# -CIU_20260909.net
KiCad netlist of a schematic drawn in Altium Designer
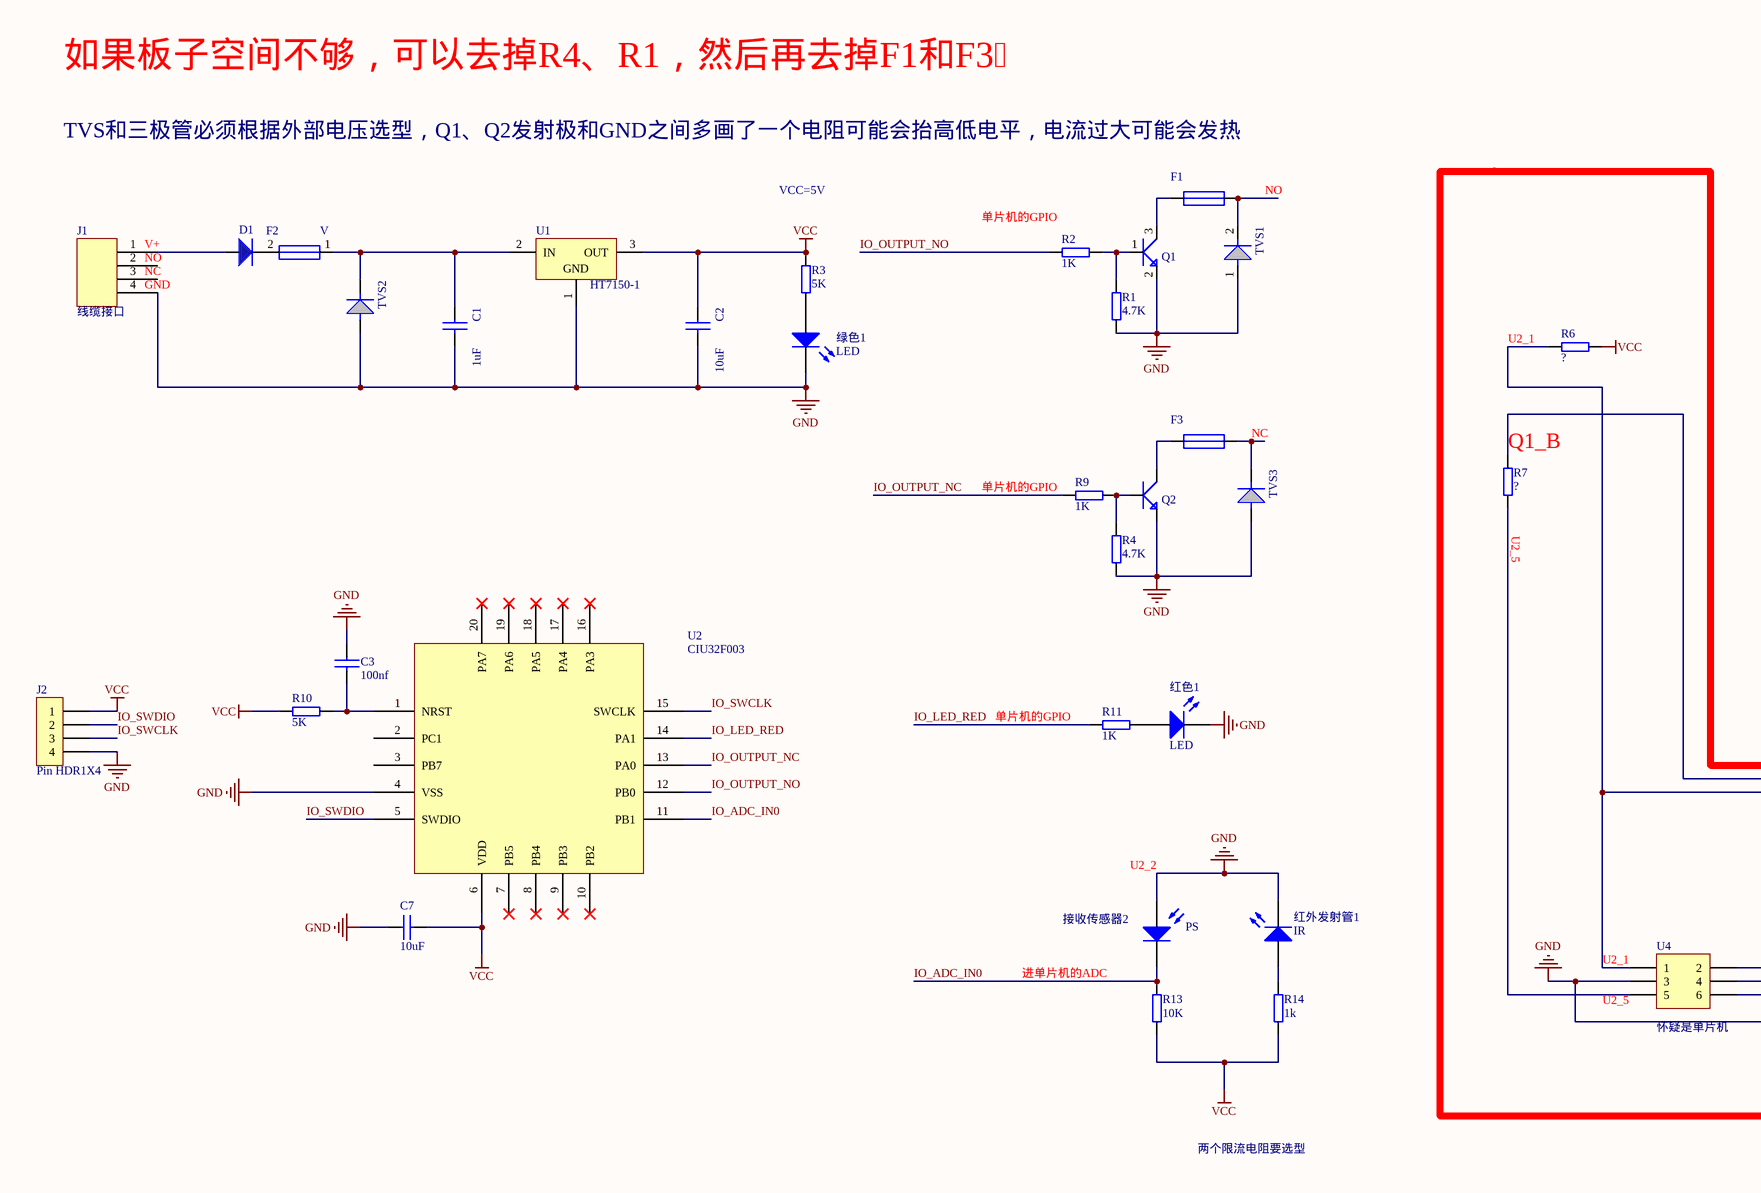
[diagram p0: 槽形开关-CIU版本20260909.SchDoc, left]
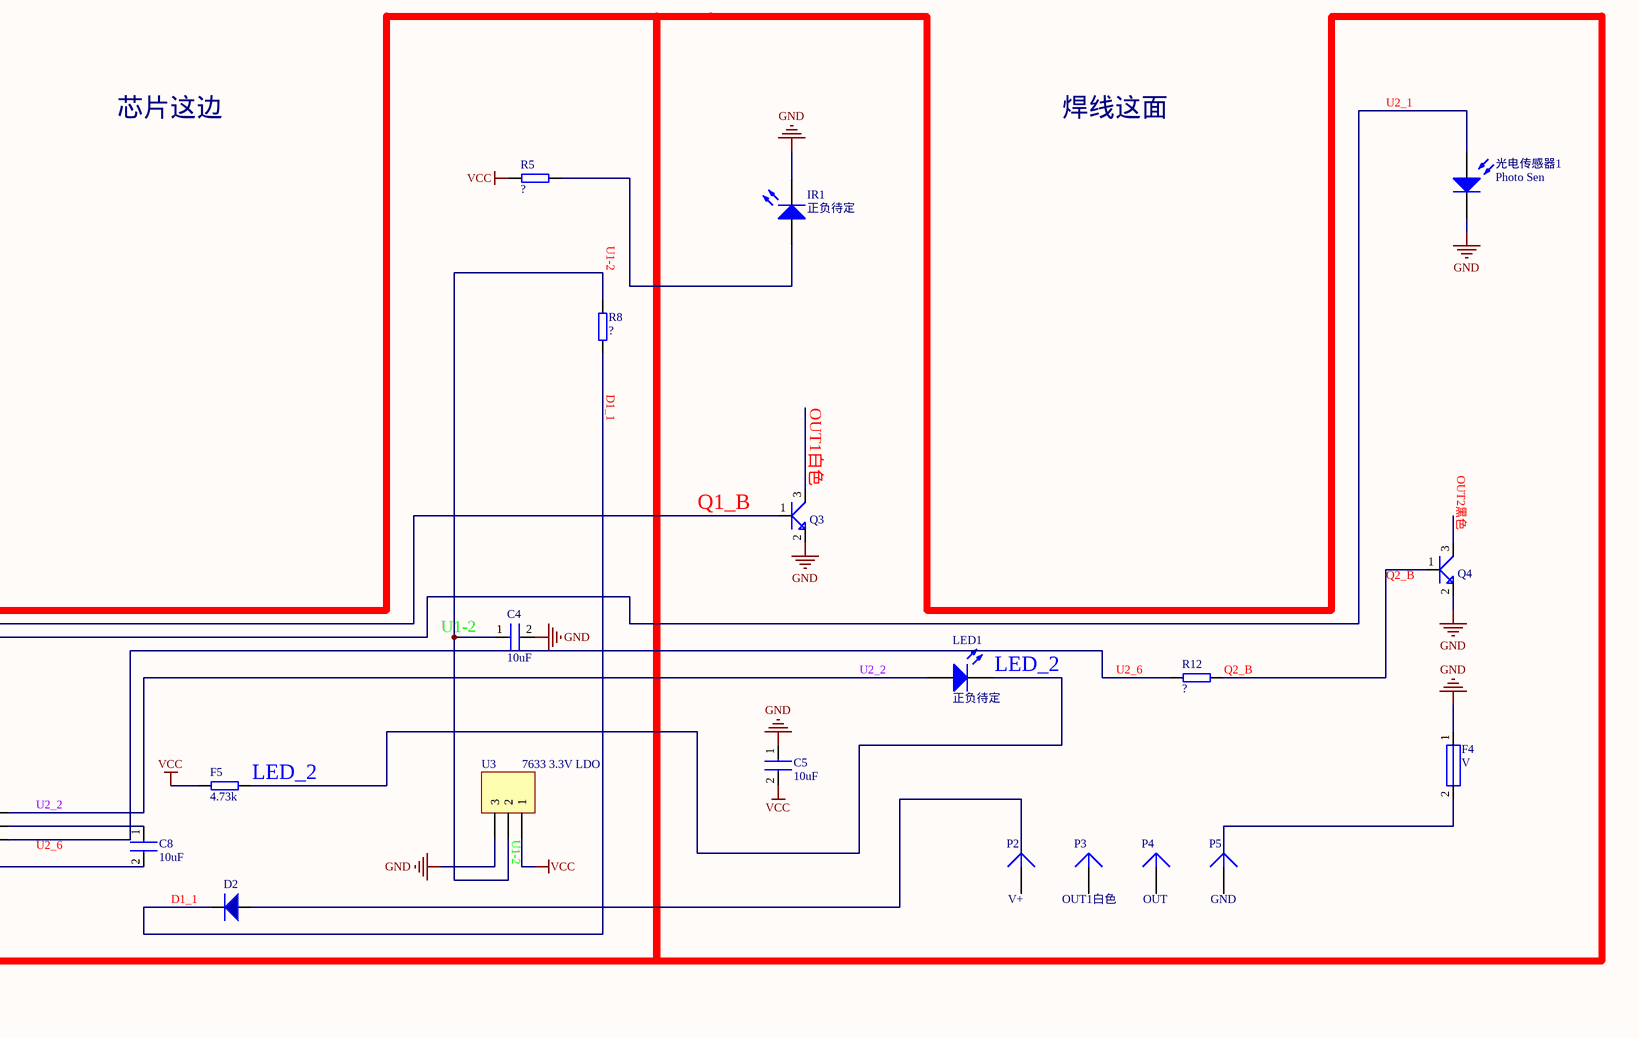
[diagram p1: 槽形开关-CIU版本20260909.SchDoc, right]

(export (version "E")
  (design (tool "Eeschema 10.0.6"))
  (components
    (comp (ref "C1") (value "1uF") (footprint "1206") (libsource (lib "*") (part "CAP NP")))
    (comp (ref "C2") (value "10uF") (footprint "1206") (libsource (lib "*") (part "CAP NP")))
    (comp (ref "C3") (value "100nf") (footprint "1206") (libsource (lib "*") (part "CAP NP")))
    (comp (ref "C4") (value "10uF") (libsource (lib "*") (part "CAP")))
    (comp (ref "C5") (value "10uF") (libsource (lib "*") (part "CAP")))
    (comp (ref "C7") (value "10uF") (footprint "1206") (libsource (lib "*") (part "CAP NP")))
    (comp (ref "C8") (value "10uF") (libsource (lib "*") (part "CAP")))
    (comp (ref "D1") (value "~") (libsource (lib "*") (part "D")))
    (comp (ref "D2") (value "~") (libsource (lib "*") (part "D")))
    (comp (ref "F1") (value "V") (footprint "0805") (libsource (lib "*") (part "FUSE_0")))
    (comp (ref "F2") (value "V") (footprint "0805") (libsource (lib "") (part "FUSE_0_2")))
    (comp (ref "F3") (value "~") (footprint "0805") (libsource (lib "*") (part "FUSE_0")))
    (comp (ref "F4") (value "V") (footprint "0805") (libsource (lib "") (part "FUSE_0_1")))
    (comp (ref "F5") (value "4.73k") (libsource (lib "*") (part "RES")))
    (comp (ref "IR1")
      (value "正负待定")
      (footprint "LED-0")
      (description "Typical INFRARED GaAs LED")
      (fields (field (name "PUBLISHER") "Altium Limited"))
      (libsource (lib "Miscellaneous Devices") (part "LED0"))
    )
    (comp (ref "J1") (value "线缆接口") (footprint "SIP4") (libsource (lib "*") (part "4H")))
    (comp (ref "J2")
      (value "Pin HDR1X4")
      (footprint "Pin HDR1X4/2.54mm-S")
      (libsource (lib "排针") (part "Pin HDR1X4"))
    )
    (comp (ref "LED1")
      (value "正负待定")
      (footprint "LED-0")
      (description "Typical INFRARED GaAs LED")
      (fields (field (name "PUBLISHER") "Altium Limited"))
      (libsource (lib "Miscellaneous Devices") (part "LED0"))
    )
    (comp (ref "P2")
      (value "V+")
      (footprint "PIN1")
      (description "Plug")
      (fields (field (name "PUBLISHER") "Altium Limited"))
      (libsource (lib "Miscellaneous Connectors") (part "Plug"))
    )
    (comp (ref "P3")
      (value "OUT1白色")
      (footprint "PIN1")
      (description "Plug")
      (fields (field (name "PUBLISHER") "Altium Limited"))
      (libsource (lib "Miscellaneous Connectors") (part "Plug"))
    )
    (comp (ref "P4")
      (value "OUT")
      (footprint "PIN1")
      (description "Plug")
      (fields (field (name "PUBLISHER") "Altium Limited"))
      (libsource (lib "Miscellaneous Connectors") (part "Plug"))
    )
    (comp (ref "P5")
      (value "GND")
      (footprint "PIN1")
      (description "Plug")
      (fields (field (name "PUBLISHER") "Altium Limited"))
      (libsource (lib "Miscellaneous Connectors") (part "Plug"))
    )
    (comp (ref "Q1") (value "2SC4617TLR") (libsource (lib "") (part "2SC4617_1")))
    (comp (ref "Q2") (value "2SC4617TLR") (libsource (lib "*") (part "2SC4617")))
    (comp (ref "Q3") (value "2SC4617TLR") (libsource (lib "") (part "2SC4617_1")))
    (comp (ref "Q4") (value "2SC4617TLR") (libsource (lib "") (part "2SC4617_1")))
    (comp (ref "R1") (value "4.7K") (libsource (lib "*") (part "RES")))
    (comp (ref "R2") (value "1K") (libsource (lib "*") (part "RES")))
    (comp (ref "R3") (value "5K") (libsource (lib "*") (part "RES")))
    (comp (ref "R4") (value "4.7K") (libsource (lib "*") (part "RES")))
    (comp (ref "R5") (value "?") (libsource (lib "*") (part "RES")))
    (comp (ref "R6") (value "?") (libsource (lib "*") (part "RES")))
    (comp (ref "R7") (value "?") (libsource (lib "*") (part "RES")))
    (comp (ref "R8") (value "?") (libsource (lib "*") (part "RES")))
    (comp (ref "R9") (value "1K") (libsource (lib "*") (part "RES")))
    (comp (ref "R10") (value "5K") (libsource (lib "*") (part "RES")))
    (comp (ref "R11") (value "1K") (libsource (lib "*") (part "RES")))
    (comp (ref "R12") (value "?") (libsource (lib "*") (part "RES")))
    (comp (ref "R13") (value "10K") (libsource (lib "*") (part "RES")))
    (comp (ref "R14") (value "1k") (libsource (lib "*") (part "RES")))
    (comp (ref "TVS1") (value "~") (footprint "1206") (libsource (lib "") (part "D1N3063_0_1")))
    (comp (ref "TVS2") (value "M1") (footprint "1206") (libsource (lib "*") (part "D1N3063_0")))
    (comp (ref "TVS3") (value "~") (footprint "1206") (libsource (lib "*") (part "D1N3063_0")))
    (comp (ref "U1")
      (value "HT7150-1")
      (footprint "SOT89N")
      (description "3.0V 100mA Low Power,  Low Dropout Voltage (LDO) Regulator")
      (fields (field (name "PUBLISHER") "Altium Limited"))
      (libsource (lib "Holtek Power Mgt Voltage Regulator") (part "HT7530-1"))
    )
    (comp (ref "U2") (value "CIU32F003") (libsource (lib "wwrDevice") (part "CIU32F003F5Uxx")))
    (comp (ref "U3")
      (value "7633 3.3V LDO")
      (footprint "HDR1X3")
      (description "Header, 3-Pin")
      (fields (field (name "PUBLISHER") "Altium Limited"))
      (libsource (lib "Miscellaneous Connectors") (part "Header 3"))
    )
    (comp (ref "U4")
      (value "怀疑是单片机")
      (footprint "HDR2X3")
      (description "Header, 3-Pin, Dual row")
      (fields (field (name "PUBLISHER") "Altium Limited"))
      (libsource (lib "Miscellaneous Connectors") (part "Header 3X2"))
    )
    (comp (ref "光电传感器1")
      (value "Photo Sen")
      (footprint "PIN2")
      (description "Photosensitive Diode")
      (fields (field (name "PUBLISHER") "Altium Limited"))
      (libsource (lib "Miscellaneous Devices") (part "Photo Sen"))
    )
    (comp (ref "接收传感器2")
      (value "PS")
      (footprint "PIN2")
      (description "Photosensitive Diode")
      (fields (field (name "PUBLISHER") "Altium Limited"))
      (libsource (lib "Miscellaneous Devices") (part "Photo Sen"))
    )
    (comp (ref "红外发射管1")
      (value "IR")
      (footprint "LED-0")
      (description "Typical INFRARED GaAs LED")
      (fields (field (name "PUBLISHER") "Altium Limited"))
      (libsource (lib "Miscellaneous Devices") (part "LED0"))
    )
    (comp (ref "红色1")
      (value "LED")
      (footprint "LED-0")
      (description "Typical INFRARED GaAs LED")
      (fields (field (name "PUBLISHER") "Altium Limited"))
      (libsource (lib "Miscellaneous Devices") (part "LED0"))
    )
    (comp (ref "绿色1")
      (value "LED")
      (footprint "LED-0")
      (description "Typical INFRARED GaAs LED")
      (fields (field (name "PUBLISHER") "Altium Limited"))
      (libsource (lib "Miscellaneous Devices") (part "LED0"))
    )
  )
  (nets
    (net (code "1") (name "/IO_ADC_IN0") (class "Default")
      (node (ref "R13") (pin "2") (pinfunction "2_2") (pintype "passive"))
      (node (ref "U2") (pin "11") (pinfunction "PB1_11") (pintype "passive"))
      (node (ref "接收传感器2") (pin "2") (pinfunction "K_2") (pintype "passive"))
    )
    (net (code "2") (name "/IO_LED_RED") (class "Default")
      (node (ref "R11") (pin "1") (pinfunction "1_1") (pintype "passive"))
      (node (ref "U2") (pin "14") (pinfunction "PA1_14") (pintype "passive"))
    )
    (net (code "3") (name "/IO_OUTPUT_NC") (class "Default")
      (node (ref "R9") (pin "1") (pinfunction "1_1") (pintype "passive"))
      (node (ref "U2") (pin "13") (pinfunction "PA0_13") (pintype "passive"))
    )
    (net (code "4") (name "/IO_OUTPUT_NO") (class "Default")
      (node (ref "R2") (pin "1") (pinfunction "1_1") (pintype "passive"))
      (node (ref "U2") (pin "12") (pinfunction "PB0_12") (pintype "passive"))
    )
    (net (code "5") (name "/IO_SWCLK") (class "Default")
      (node (ref "J2") (pin "3") (pinfunction "3_3") (pintype "passive"))
      (node (ref "U2") (pin "15") (pinfunction "SWCLK_15") (pintype "passive"))
    )
    (net (code "6") (name "/IO_SWDIO") (class "Default")
      (node (ref "J2") (pin "2") (pinfunction "2_2") (pintype "passive"))
      (node (ref "U2") (pin "5") (pinfunction "SWDIO_5") (pintype "passive"))
    )
    (net (code "7") (name "GND") (class "Default")
      (node (ref "C1") (pin "2") (pinfunction "2_2") (pintype "passive"))
      (node (ref "C2") (pin "2") (pinfunction "2_2") (pintype "passive"))
      (node (ref "C3") (pin "1") (pinfunction "1_1") (pintype "passive"))
      (node (ref "C4") (pin "2") (pintype "passive"))
      (node (ref "C5") (pin "1") (pintype "passive"))
      (node (ref "C7") (pin "1") (pinfunction "1_1") (pintype "passive"))
      (node (ref "C8") (pin "2") (pintype "passive"))
      (node (ref "F4") (pin "1") (pinfunction "1_1") (pintype "passive"))
      (node (ref "IR1") (pin "2") (pinfunction "K_2") (pintype "passive"))
      (node (ref "J1") (pin "4") (pintype "passive"))
      (node (ref "J2") (pin "4") (pinfunction "4_4") (pintype "passive"))
      (node (ref "Q1") (pin "2") (pinfunction "E_2") (pintype "passive"))
      (node (ref "Q2") (pin "2") (pinfunction "E_2") (pintype "passive"))
      (node (ref "Q3") (pin "2") (pinfunction "E_2") (pintype "passive"))
      (node (ref "Q4") (pin "2") (pinfunction "E_2") (pintype "passive"))
      (node (ref "R1") (pin "2") (pinfunction "2_2") (pintype "passive"))
      (node (ref "R4") (pin "2") (pinfunction "2_2") (pintype "passive"))
      (node (ref "TVS1") (pin "1") (pinfunction "1_1") (pintype "passive"))
      (node (ref "TVS2") (pin "1") (pinfunction "1_1") (pintype "passive"))
      (node (ref "TVS3") (pin "1") (pinfunction "1_1") (pintype "passive"))
      (node (ref "U1") (pin "1") (pinfunction "GND_1") (pintype "power_in"))
      (node (ref "U2") (pin "4") (pinfunction "VSS_4") (pintype "passive"))
      (node (ref "U3") (pin "3") (pinfunction "3_3") (pintype "passive"))
      (node (ref "U4") (pin "3") (pinfunction "3_3") (pintype "passive"))
      (node (ref "光电传感器1") (pin "2") (pinfunction "K_2") (pintype "passive"))
      (node (ref "接收传感器2") (pin "1") (pinfunction "A_1") (pintype "passive"))
      (node (ref "红外发射管1") (pin "2") (pinfunction "K_2") (pintype "passive"))
      (node (ref "红色1") (pin "2") (pinfunction "K_2") (pintype "passive"))
      (node (ref "绿色1") (pin "2") (pinfunction "K_2") (pintype "passive"))
    )
    (net (code "8") (name "Net-(C4-Pad1)") (class "Default")
      (node (ref "C4") (pin "1") (pintype "passive"))
      (node (ref "R8") (pin "2") (pinfunction "2_2") (pintype "passive"))
      (node (ref "U3") (pin "2") (pinfunction "2_2") (pintype "passive"))
    )
    (net (code "9") (name "Net-(C8-Pad1)") (class "Default")
      (node (ref "C8") (pin "1") (pintype "passive"))
      (node (ref "U4") (pin "4") (pinfunction "4_4") (pintype "passive"))
    )
    (net (code "10") (name "Net-(D1-Pad1)") (class "Default")
      (node (ref "D1") (pin "1") (pintype "passive"))
      (node (ref "J1") (pin "1") (pintype "passive"))
    )
    (net (code "11") (name "Net-(D1-Pad2)") (class "Default")
      (node (ref "D1") (pin "2") (pintype "passive"))
      (node (ref "F2") (pin "2") (pinfunction "2_2") (pintype "passive"))
    )
    (net (code "12") (name "Net-(D2-Pad2)") (class "Default")
      (node (ref "D2") (pin "2") (pintype "passive"))
      (node (ref "R8") (pin "1") (pinfunction "1_1") (pintype "passive"))
    )
    (net (code "13") (name "Net-(F1-Pad1)") (class "Default")
      (node (ref "F1") (pin "1") (pinfunction "1_1") (pintype "passive"))
      (node (ref "TVS1") (pin "2") (pinfunction "2_2") (pintype "passive"))
    )
    (net (code "14") (name "Net-(F3-Pad1)") (class "Default")
      (node (ref "F3") (pin "1") (pinfunction "1_1") (pintype "passive"))
      (node (ref "TVS3") (pin "2") (pinfunction "2_2") (pintype "passive"))
    )
    (net (code "15") (name "Net-(IR1-A)") (class "Default")
      (node (ref "IR1") (pin "1") (pinfunction "A_1") (pintype "passive"))
      (node (ref "R5") (pin "1") (pinfunction "1_1") (pintype "passive"))
    )
    (net (code "16") (name "Net-(LED1-A)") (class "Default")
      (node (ref "LED1") (pin "1") (pinfunction "A_1") (pintype "passive"))
      (node (ref "U4") (pin "2") (pinfunction "2_2") (pintype "passive"))
    )
    (net (code "17") (name "Net-(LED1-K)") (class "Default")
      (node (ref "F5") (pin "1") (pinfunction "1_1") (pintype "passive"))
      (node (ref "LED1") (pin "2") (pinfunction "K_2") (pintype "passive"))
    )
    (net (code "18") (name "Net-(Q1-B)") (class "Default")
      (node (ref "Q1") (pin "1") (pinfunction "B_1") (pintype "passive"))
      (node (ref "R1") (pin "1") (pinfunction "1_1") (pintype "passive"))
      (node (ref "R2") (pin "2") (pinfunction "2_2") (pintype "passive"))
    )
    (net (code "19") (name "Net-(Q1-C)") (class "Default")
      (node (ref "F1") (pin "2") (pinfunction "2_2") (pintype "passive"))
      (node (ref "Q1") (pin "3") (pinfunction "C_3") (pintype "passive"))
    )
    (net (code "20") (name "Net-(Q2-B)") (class "Default")
      (node (ref "Q2") (pin "1") (pinfunction "B_1") (pintype "passive"))
      (node (ref "R4") (pin "1") (pinfunction "1_1") (pintype "passive"))
      (node (ref "R9") (pin "2") (pinfunction "2_2") (pintype "passive"))
    )
    (net (code "21") (name "Net-(Q2-C)") (class "Default")
      (node (ref "F3") (pin "2") (pinfunction "2_2") (pintype "passive"))
      (node (ref "Q2") (pin "3") (pinfunction "C_3") (pintype "passive"))
    )
    (net (code "22") (name "Net-(Q3-B)") (class "Default")
      (node (ref "Q3") (pin "1") (pinfunction "B_1") (pintype "passive"))
      (node (ref "R7") (pin "2") (pinfunction "2_2") (pintype "passive"))
    )
    (net (code "23") (name "Net-(Q4-B)") (class "Default")
      (node (ref "Q4") (pin "1") (pinfunction "B_1") (pintype "passive"))
      (node (ref "R12") (pin "1") (pinfunction "1_1") (pintype "passive"))
    )
    (net (code "24") (name "Net-(R7-Pad1)") (class "Default")
      (node (ref "R7") (pin "1") (pinfunction "1_1") (pintype "passive"))
      (node (ref "U4") (pin "5") (pinfunction "5_5") (pintype "passive"))
    )
    (net (code "25") (name "Net-(R12-Pad2)") (class "Default")
      (node (ref "R12") (pin "2") (pinfunction "2_2") (pintype "passive"))
      (node (ref "U4") (pin "6") (pinfunction "6_6") (pintype "passive"))
    )
    (net (code "26") (name "Net-(U1-IN)") (class "Default")
      (node (ref "C1") (pin "1") (pinfunction "1_1") (pintype "passive"))
      (node (ref "F2") (pin "1") (pinfunction "1_1") (pintype "passive"))
      (node (ref "TVS2") (pin "2") (pinfunction "2_2") (pintype "passive"))
      (node (ref "U1") (pin "2") (pinfunction "IN_2") (pintype "power_in"))
    )
    (net (code "27") (name "Net-(U2-NRST)") (class "Default")
      (node (ref "C3") (pin "2") (pinfunction "2_2") (pintype "passive"))
      (node (ref "R10") (pin "1") (pinfunction "1_1") (pintype "passive"))
      (node (ref "U2") (pin "1") (pinfunction "NRST_1") (pintype "passive"))
    )
    (net (code "28") (name "Net-(光电传感器1-A)") (class "Default")
      (node (ref "R6") (pin "2") (pinfunction "2_2") (pintype "passive"))
      (node (ref "U4") (pin "1") (pinfunction "1_1") (pintype "passive"))
      (node (ref "光电传感器1") (pin "1") (pinfunction "A_1") (pintype "passive"))
    )
    (net (code "29") (name "Net-(红外发射管1-A)") (class "Default")
      (node (ref "R14") (pin "2") (pinfunction "2_2") (pintype "passive"))
      (node (ref "红外发射管1") (pin "1") (pinfunction "A_1") (pintype "passive"))
    )
    (net (code "30") (name "Net-(红色1-A)") (class "Default")
      (node (ref "R11") (pin "2") (pinfunction "2_2") (pintype "passive"))
      (node (ref "红色1") (pin "1") (pinfunction "A_1") (pintype "passive"))
    )
    (net (code "31") (name "Net-(绿色1-A)") (class "Default")
      (node (ref "R3") (pin "2") (pinfunction "2_2") (pintype "passive"))
      (node (ref "绿色1") (pin "1") (pinfunction "A_1") (pintype "passive"))
    )
    (net (code "32") (name "VCC") (class "Default")
      (node (ref "C2") (pin "1") (pinfunction "1_1") (pintype "passive"))
      (node (ref "C5") (pin "2") (pintype "passive"))
      (node (ref "C7") (pin "2") (pinfunction "2_2") (pintype "passive"))
      (node (ref "F5") (pin "2") (pinfunction "2_2") (pintype "passive"))
      (node (ref "J2") (pin "1") (pinfunction "1_1") (pintype "passive"))
      (node (ref "R10") (pin "2") (pinfunction "2_2") (pintype "passive"))
      (node (ref "R13") (pin "1") (pinfunction "1_1") (pintype "passive"))
      (node (ref "R14") (pin "1") (pinfunction "1_1") (pintype "passive"))
      (node (ref "R3") (pin "1") (pinfunction "1_1") (pintype "passive"))
      (node (ref "R5") (pin "2") (pinfunction "2_2") (pintype "passive"))
      (node (ref "R6") (pin "1") (pinfunction "1_1") (pintype "passive"))
      (node (ref "U1") (pin "3") (pinfunction "OUT_3") (pintype "power_in"))
      (node (ref "U2") (pin "6") (pinfunction "VDD_6") (pintype "passive"))
      (node (ref "U3") (pin "1") (pinfunction "1_1") (pintype "passive"))
    )
    (net (code "33") (name "unconnected-(D2-Pad1)") (class "Default")
      (node (ref "D2") (pin "1") (pintype "passive"))
    )
    (net (code "34") (name "unconnected-(F4-Pad2)") (class "Default")
      (node (ref "F4") (pin "2") (pinfunction "2_2") (pintype "passive"))
    )
    (net (code "35") (name "unconnected-(J1-Pad2)") (class "Default")
      (node (ref "J1") (pin "2") (pintype "passive"))
    )
    (net (code "36") (name "unconnected-(J1-Pad3)") (class "Default")
      (node (ref "J1") (pin "3") (pintype "passive"))
    )
    (net (code "37") (name "unconnected-(P2-Pad1)") (class "Default")
      (node (ref "P2") (pin "1") (pinfunction "1_1") (pintype "passive"))
    )
    (net (code "38") (name "unconnected-(P3-Pad1)") (class "Default")
      (node (ref "P3") (pin "1") (pinfunction "1_1") (pintype "passive"))
    )
    (net (code "39") (name "unconnected-(P4-Pad1)") (class "Default")
      (node (ref "P4") (pin "1") (pinfunction "1_1") (pintype "passive"))
    )
    (net (code "40") (name "unconnected-(P5-Pad1)") (class "Default")
      (node (ref "P5") (pin "1") (pinfunction "1_1") (pintype "passive"))
    )
    (net (code "41") (name "unconnected-(Q3-C-Pad3)") (class "Default")
      (node (ref "Q3") (pin "3") (pinfunction "C_3") (pintype "passive"))
    )
    (net (code "42") (name "unconnected-(Q4-C-Pad3)") (class "Default")
      (node (ref "Q4") (pin "3") (pinfunction "C_3") (pintype "passive"))
    )
    (net (code "43") (name "unconnected-(U2-PA3-Pad16)") (class "Default")
      (node (ref "U2") (pin "16") (pinfunction "PA3_16") (pintype "passive+no_connect"))
    )
    (net (code "44") (name "unconnected-(U2-PA4-Pad17)") (class "Default")
      (node (ref "U2") (pin "17") (pinfunction "PA4_17") (pintype "passive+no_connect"))
    )
    (net (code "45") (name "unconnected-(U2-PA5-Pad18)") (class "Default")
      (node (ref "U2") (pin "18") (pinfunction "PA5_18") (pintype "passive+no_connect"))
    )
    (net (code "46") (name "unconnected-(U2-PA6-Pad19)") (class "Default")
      (node (ref "U2") (pin "19") (pinfunction "PA6_19") (pintype "passive+no_connect"))
    )
    (net (code "47") (name "unconnected-(U2-PA7-Pad20)") (class "Default")
      (node (ref "U2") (pin "20") (pinfunction "PA7_20") (pintype "passive+no_connect"))
    )
    (net (code "48") (name "unconnected-(U2-PB2-Pad10)") (class "Default")
      (node (ref "U2") (pin "10") (pinfunction "PB2_10") (pintype "passive+no_connect"))
    )
    (net (code "49") (name "unconnected-(U2-PB3-Pad9)") (class "Default")
      (node (ref "U2") (pin "9") (pinfunction "PB3_9") (pintype "passive+no_connect"))
    )
    (net (code "50") (name "unconnected-(U2-PB4-Pad8)") (class "Default")
      (node (ref "U2") (pin "8") (pinfunction "PB4_8") (pintype "passive+no_connect"))
    )
    (net (code "51") (name "unconnected-(U2-PB5-Pad7)") (class "Default")
      (node (ref "U2") (pin "7") (pinfunction "PB5_7") (pintype "passive+no_connect"))
    )
    (net (code "52") (name "unconnected-(U2-PB7-Pad3)") (class "Default")
      (node (ref "U2") (pin "3") (pinfunction "PB7_3") (pintype "passive"))
    )
    (net (code "53") (name "unconnected-(U2-PC1-Pad2)") (class "Default")
      (node (ref "U2") (pin "2") (pinfunction "PC1_2") (pintype "passive"))
    )
  )
)
